# PLD_RadFET_Supply.net
KiCad netlist of a schematic drawn in Altium Designer
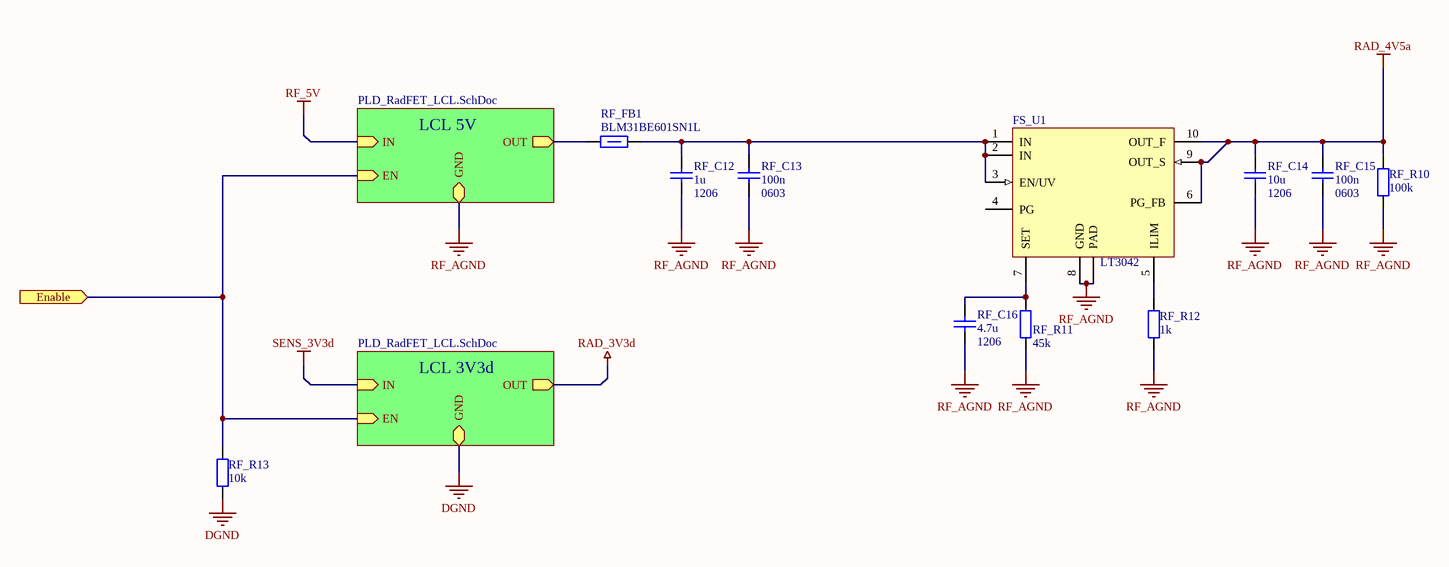
[diagram p0: PLD_RadFET_Supply.SchDoc]

(export (version "E")
  (design (tool "Eeschema 10.0.6"))
  (components
    (comp (ref "FS_U1")
      (value "LT3042")
      (footprint "MSOP-10-M-thermal-pad")
      (description "20V, 200mA, Ultralow Noise, Ultrahigh PSRR RF Linear Regulator")
      (libsource (lib "microcircuits") (part "LT3042"))
    )
    (comp (ref "RF_C12")
      (value "1u")
      (footprint "SMD_Capacitor_1206")
      (description "Cap")
      (fields (field (name "PACKAGE") "1206"))
      (libsource (lib "capacitors") (part "Cap"))
    )
    (comp (ref "RF_C13")
      (value "100n")
      (footprint "SMD_Capacitor_0603")
      (description "Cap")
      (fields (field (name "PACKAGE") "0603"))
      (libsource (lib "capacitors") (part "Cap"))
    )
    (comp (ref "RF_C14")
      (value "10u")
      (footprint "SMD_Capacitor_1206")
      (description "Cap")
      (fields (field (name "PACKAGE") "1206"))
      (libsource (lib "capacitors") (part "Cap"))
    )
    (comp (ref "RF_C15")
      (value "100n")
      (footprint "SMD_Capacitor_0603")
      (description "Cap")
      (fields (field (name "PACKAGE") "0603"))
      (libsource (lib "capacitors") (part "Cap"))
    )
    (comp (ref "RF_C16")
      (value "4.7u")
      (footprint "SMD_Capacitor_1206")
      (description "Cap")
      (fields (field (name "PACKAGE") "1206"))
      (libsource (lib "capacitors") (part "Cap"))
    )
    (comp (ref "RF_FB1")
      (value "600R/100MHz")
      (footprint "1206")
      (description "Ferrite Bead")
      (fields (field (name "MANUFACTURER") "Murata") (field (name "MANUFACTURERPARTNUMBER") "BLM31BE601SN1L"))
      (libsource (lib "inductors") (part "FerriteBead"))
    )
    (comp (ref "RF_R10")
      (value "100k")
      (footprint "SMD_Resistor_0603")
      (libsource (lib "resistors") (part "Res"))
    )
    (comp (ref "RF_R11")
      (value "45k")
      (footprint "SMD_Resistor_0603")
      (libsource (lib "resistors") (part "Res"))
    )
    (comp (ref "RF_R12")
      (value "1k")
      (footprint "SMD_Resistor_0603")
      (libsource (lib "resistors") (part "Res"))
    )
    (comp (ref "RF_R13")
      (value "10k")
      (footprint "SMD_Resistor_0603")
      (libsource (lib "resistors") (part "Res"))
    )
  )
  (nets
    (net (code "1") (name "/Enable") (class "Default")
      (node (ref "RF_R13") (pin "2") (pinfunction "2_2") (pintype "passive"))
    )
    (net (code "2") (name "/OUT") (class "Default")
      (node (ref "RF_FB1") (pin "2") (pinfunction "2_2") (pintype "passive"))
    )
    (net (code "3") (name "DGND") (class "Default")
      (node (ref "RF_R13") (pin "1") (pinfunction "1_1") (pintype "passive"))
    )
    (net (code "4") (name "Net-(FS_U1-EN{slash}UV)") (class "Default")
      (node (ref "FS_U1") (pin "1") (pinfunction "IN_1") (pintype "power_in"))
      (node (ref "FS_U1") (pin "2") (pinfunction "IN_2") (pintype "power_in"))
      (node (ref "FS_U1") (pin "3") (pinfunction "EN/UV_3") (pintype "input"))
      (node (ref "RF_C12") (pin "1") (pinfunction "1_1") (pintype "passive"))
      (node (ref "RF_C13") (pin "1") (pinfunction "1_1") (pintype "passive"))
      (node (ref "RF_FB1") (pin "1") (pinfunction "1_1") (pintype "passive"))
    )
    (net (code "5") (name "Net-(FS_U1-ILIM)") (class "Default")
      (node (ref "FS_U1") (pin "5") (pinfunction "ILIM_5") (pintype "passive"))
      (node (ref "RF_R12") (pin "2") (pinfunction "2_2") (pintype "passive"))
    )
    (net (code "6") (name "Net-(FS_U1-SET)") (class "Default")
      (node (ref "FS_U1") (pin "7") (pinfunction "SET_7") (pintype "passive"))
      (node (ref "RF_C16") (pin "1") (pinfunction "1_1") (pintype "passive"))
      (node (ref "RF_R11") (pin "2") (pinfunction "2_2") (pintype "passive"))
    )
    (net (code "8") (name "RAD_4V5a") (class "Default")
      (node (ref "FS_U1") (pin "10") (pinfunction "OUT_F_10") (pintype "power_in"))
      (node (ref "FS_U1") (pin "6") (pinfunction "PG_FB_6") (pintype "passive"))
      (node (ref "FS_U1") (pin "9") (pinfunction "OUT_S_9") (pintype "input"))
      (node (ref "RF_C14") (pin "1") (pinfunction "1_1") (pintype "passive"))
      (node (ref "RF_C15") (pin "1") (pinfunction "1_1") (pintype "passive"))
      (node (ref "RF_R10") (pin "2") (pinfunction "2_2") (pintype "passive"))
    )
    (net (code "10") (name "RF_AGND") (class "Default")
      (node (ref "FS_U1") (pin "11") (pinfunction "PAD_11") (pintype "power_in"))
      (node (ref "FS_U1") (pin "8") (pinfunction "GND_8") (pintype "power_in"))
      (node (ref "RF_C12") (pin "2") (pinfunction "2_2") (pintype "passive"))
      (node (ref "RF_C13") (pin "2") (pinfunction "2_2") (pintype "passive"))
      (node (ref "RF_C14") (pin "2") (pinfunction "2_2") (pintype "passive"))
      (node (ref "RF_C15") (pin "2") (pinfunction "2_2") (pintype "passive"))
      (node (ref "RF_C16") (pin "2") (pinfunction "2_2") (pintype "passive"))
      (node (ref "RF_R10") (pin "1") (pinfunction "1_1") (pintype "passive"))
      (node (ref "RF_R11") (pin "1") (pinfunction "1_1") (pintype "passive"))
      (node (ref "RF_R12") (pin "1") (pinfunction "1_1") (pintype "passive"))
    )
    (net (code "12") (name "unconnected-(FS_U1-PG-Pad4)") (class "Default")
      (node (ref "FS_U1") (pin "4") (pinfunction "PG_4") (pintype "power_in"))
    )
  )
)
